# Timer_Register.net
KiCad netlist of a schematic drawn in Altium Designer
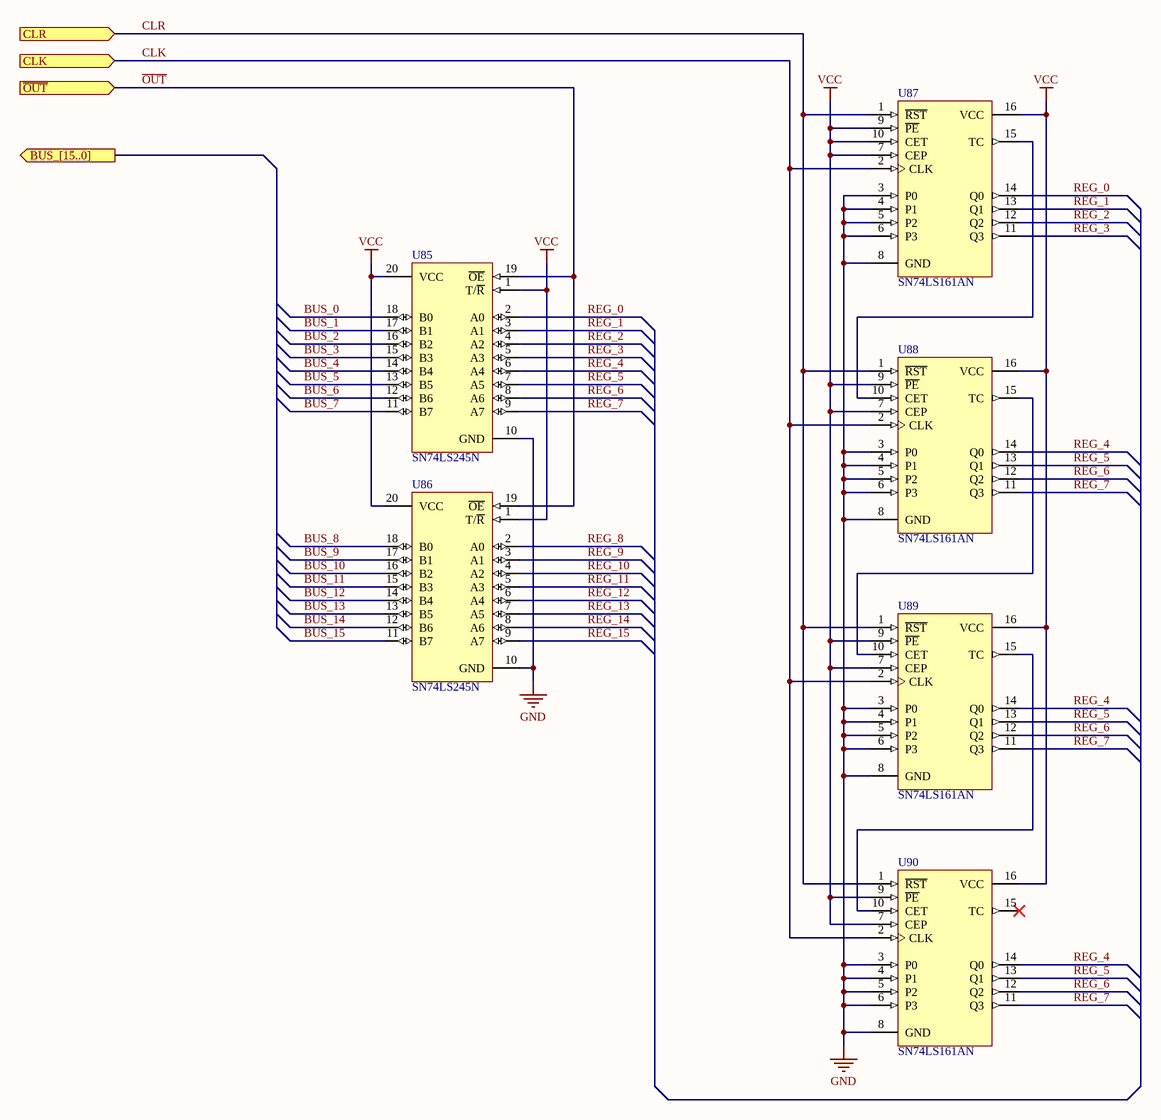
[diagram p0: Timer_Register.SchDoc]

(export (version "E")
  (design (tool "Eeschema 10.0.6"))
  (components
    (comp (ref "U85")
      (value "SN74LS245N")
      (footprint "N020")
      (description "Octal Bus Transceiver with 3-State Outputs")
      (fields (field (name "PUBLISHER") "Altium Limited"))
      (libsource (lib "TI Interface 8-Bit Line Transceiver") (part "SN74LS245N"))
    )
    (comp (ref "U86")
      (value "SN74LS245N")
      (footprint "N020")
      (description "Octal Bus Transceiver with 3-State Outputs")
      (fields (field (name "PUBLISHER") "Altium Limited"))
      (libsource (lib "TI Interface 8-Bit Line Transceiver") (part "SN74LS245N"))
    )
    (comp (ref "U87")
      (value "SN74LS161AN")
      (footprint "N016")
      (description "Synchronous 4-Bit Counter")
      (fields (field (name "PUBLISHER") "Altium Limited"))
      (libsource (lib "TI Logic Counter") (part "SN74LS161AN"))
    )
    (comp (ref "U88")
      (value "SN74LS161AN")
      (footprint "N016")
      (description "Synchronous 4-Bit Counter")
      (fields (field (name "PUBLISHER") "Altium Limited"))
      (libsource (lib "TI Logic Counter") (part "SN74LS161AN"))
    )
    (comp (ref "U89")
      (value "SN74LS161AN")
      (footprint "N016")
      (description "Synchronous 4-Bit Counter")
      (fields (field (name "PUBLISHER") "Altium Limited"))
      (libsource (lib "TI Logic Counter") (part "SN74LS161AN"))
    )
    (comp (ref "U90")
      (value "SN74LS161AN")
      (footprint "N016")
      (description "Synchronous 4-Bit Counter")
      (fields (field (name "PUBLISHER") "Altium Limited"))
      (libsource (lib "TI Logic Counter") (part "SN74LS161AN"))
    )
  )
  (nets
    (net (code "1") (name "/BUS_0") (class "Default")
      (node (ref "U85") (pin "18") (pinfunction "B0_18") (pintype "bidirectional"))
    )
    (net (code "2") (name "/BUS_1") (class "Default")
      (node (ref "U85") (pin "17") (pinfunction "B1_17") (pintype "bidirectional"))
    )
    (net (code "3") (name "/BUS_2") (class "Default")
      (node (ref "U85") (pin "16") (pinfunction "B2_16") (pintype "bidirectional"))
    )
    (net (code "4") (name "/BUS_3") (class "Default")
      (node (ref "U85") (pin "15") (pinfunction "B3_15") (pintype "bidirectional"))
    )
    (net (code "5") (name "/BUS_4") (class "Default")
      (node (ref "U85") (pin "14") (pinfunction "B4_14") (pintype "bidirectional"))
    )
    (net (code "6") (name "/BUS_5") (class "Default")
      (node (ref "U85") (pin "13") (pinfunction "B5_13") (pintype "bidirectional"))
    )
    (net (code "7") (name "/BUS_6") (class "Default")
      (node (ref "U85") (pin "12") (pinfunction "B6_12") (pintype "bidirectional"))
    )
    (net (code "8") (name "/BUS_7") (class "Default")
      (node (ref "U85") (pin "11") (pinfunction "B7_11") (pintype "bidirectional"))
    )
    (net (code "9") (name "/BUS_8") (class "Default")
      (node (ref "U86") (pin "18") (pinfunction "B0_18") (pintype "bidirectional"))
    )
    (net (code "10") (name "/BUS_9") (class "Default")
      (node (ref "U86") (pin "17") (pinfunction "B1_17") (pintype "bidirectional"))
    )
    (net (code "11") (name "/BUS_10") (class "Default")
      (node (ref "U86") (pin "16") (pinfunction "B2_16") (pintype "bidirectional"))
    )
    (net (code "12") (name "/BUS_11") (class "Default")
      (node (ref "U86") (pin "15") (pinfunction "B3_15") (pintype "bidirectional"))
    )
    (net (code "13") (name "/BUS_12") (class "Default")
      (node (ref "U86") (pin "14") (pinfunction "B4_14") (pintype "bidirectional"))
    )
    (net (code "14") (name "/BUS_13") (class "Default")
      (node (ref "U86") (pin "13") (pinfunction "B5_13") (pintype "bidirectional"))
    )
    (net (code "15") (name "/BUS_14") (class "Default")
      (node (ref "U86") (pin "12") (pinfunction "B6_12") (pintype "bidirectional"))
    )
    (net (code "16") (name "/BUS_15") (class "Default")
      (node (ref "U86") (pin "11") (pinfunction "B7_11") (pintype "bidirectional"))
    )
    (net (code "18") (name "/CLK") (class "Default")
      (node (ref "U87") (pin "2") (pinfunction "CLK_2") (pintype "input"))
      (node (ref "U88") (pin "2") (pinfunction "CLK_2") (pintype "input"))
      (node (ref "U89") (pin "2") (pinfunction "CLK_2") (pintype "input"))
      (node (ref "U90") (pin "2") (pinfunction "CLK_2") (pintype "input"))
    )
    (net (code "19") (name "/CLR") (class "Default")
      (node (ref "U87") (pin "1") (pinfunction "~{RST}_1") (pintype "input"))
      (node (ref "U88") (pin "1") (pinfunction "~{RST}_1") (pintype "input"))
      (node (ref "U89") (pin "1") (pinfunction "~{RST}_1") (pintype "input"))
      (node (ref "U90") (pin "1") (pinfunction "~{RST}_1") (pintype "input"))
    )
    (net (code "20") (name "/REG_0") (class "Default")
      (node (ref "U85") (pin "2") (pinfunction "A0_2") (pintype "bidirectional"))
      (node (ref "U87") (pin "14") (pinfunction "Q0_14") (pintype "output"))
    )
    (net (code "21") (name "/REG_1") (class "Default")
      (node (ref "U85") (pin "3") (pinfunction "A1_3") (pintype "bidirectional"))
      (node (ref "U87") (pin "13") (pinfunction "Q1_13") (pintype "output"))
    )
    (net (code "22") (name "/REG_2") (class "Default")
      (node (ref "U85") (pin "4") (pinfunction "A2_4") (pintype "bidirectional"))
      (node (ref "U87") (pin "12") (pinfunction "Q2_12") (pintype "output"))
    )
    (net (code "23") (name "/REG_3") (class "Default")
      (node (ref "U85") (pin "5") (pinfunction "A3_5") (pintype "bidirectional"))
      (node (ref "U87") (pin "11") (pinfunction "Q3_11") (pintype "output"))
    )
    (net (code "24") (name "/REG_4") (class "Default")
      (node (ref "U85") (pin "6") (pinfunction "A4_6") (pintype "bidirectional"))
      (node (ref "U88") (pin "14") (pinfunction "Q0_14") (pintype "output"))
      (node (ref "U89") (pin "14") (pinfunction "Q0_14") (pintype "output"))
      (node (ref "U90") (pin "14") (pinfunction "Q0_14") (pintype "output"))
    )
    (net (code "25") (name "/REG_5") (class "Default")
      (node (ref "U85") (pin "7") (pinfunction "A5_7") (pintype "bidirectional"))
      (node (ref "U88") (pin "13") (pinfunction "Q1_13") (pintype "output"))
      (node (ref "U89") (pin "13") (pinfunction "Q1_13") (pintype "output"))
      (node (ref "U90") (pin "13") (pinfunction "Q1_13") (pintype "output"))
    )
    (net (code "26") (name "/REG_6") (class "Default")
      (node (ref "U85") (pin "8") (pinfunction "A6_8") (pintype "bidirectional"))
      (node (ref "U88") (pin "12") (pinfunction "Q2_12") (pintype "output"))
      (node (ref "U89") (pin "12") (pinfunction "Q2_12") (pintype "output"))
      (node (ref "U90") (pin "12") (pinfunction "Q2_12") (pintype "output"))
    )
    (net (code "27") (name "/REG_7") (class "Default")
      (node (ref "U85") (pin "9") (pinfunction "A7_9") (pintype "bidirectional"))
      (node (ref "U88") (pin "11") (pinfunction "Q3_11") (pintype "output"))
      (node (ref "U89") (pin "11") (pinfunction "Q3_11") (pintype "output"))
      (node (ref "U90") (pin "11") (pinfunction "Q3_11") (pintype "output"))
    )
    (net (code "28") (name "/REG_8") (class "Default")
      (node (ref "U86") (pin "2") (pinfunction "A0_2") (pintype "bidirectional"))
    )
    (net (code "29") (name "/REG_9") (class "Default")
      (node (ref "U86") (pin "3") (pinfunction "A1_3") (pintype "bidirectional"))
    )
    (net (code "30") (name "/REG_10") (class "Default")
      (node (ref "U86") (pin "4") (pinfunction "A2_4") (pintype "bidirectional"))
    )
    (net (code "31") (name "/REG_11") (class "Default")
      (node (ref "U86") (pin "5") (pinfunction "A3_5") (pintype "bidirectional"))
    )
    (net (code "32") (name "/REG_12") (class "Default")
      (node (ref "U86") (pin "6") (pinfunction "A4_6") (pintype "bidirectional"))
    )
    (net (code "33") (name "/REG_13") (class "Default")
      (node (ref "U86") (pin "7") (pinfunction "A5_7") (pintype "bidirectional"))
    )
    (net (code "34") (name "/REG_14") (class "Default")
      (node (ref "U86") (pin "8") (pinfunction "A6_8") (pintype "bidirectional"))
    )
    (net (code "35") (name "/REG_15") (class "Default")
      (node (ref "U86") (pin "9") (pinfunction "A7_9") (pintype "bidirectional"))
    )
    (net (code "36") (name "/~{OUT}") (class "Default")
      (node (ref "U85") (pin "19") (pinfunction "~{OE}_19") (pintype "input"))
      (node (ref "U86") (pin "19") (pinfunction "~{OE}_19") (pintype "input"))
    )
    (net (code "37") (name "GND") (class "Default")
      (node (ref "U85") (pin "10") (pinfunction "GND_10") (pintype "power_in"))
      (node (ref "U86") (pin "10") (pinfunction "GND_10") (pintype "power_in"))
      (node (ref "U87") (pin "3") (pinfunction "P0_3") (pintype "input"))
      (node (ref "U87") (pin "4") (pinfunction "P1_4") (pintype "input"))
      (node (ref "U87") (pin "5") (pinfunction "P2_5") (pintype "input"))
      (node (ref "U87") (pin "6") (pinfunction "P3_6") (pintype "input"))
      (node (ref "U87") (pin "8") (pinfunction "GND_8") (pintype "power_in"))
      (node (ref "U88") (pin "3") (pinfunction "P0_3") (pintype "input"))
      (node (ref "U88") (pin "4") (pinfunction "P1_4") (pintype "input"))
      (node (ref "U88") (pin "5") (pinfunction "P2_5") (pintype "input"))
      (node (ref "U88") (pin "6") (pinfunction "P3_6") (pintype "input"))
      (node (ref "U88") (pin "8") (pinfunction "GND_8") (pintype "power_in"))
      (node (ref "U89") (pin "3") (pinfunction "P0_3") (pintype "input"))
      (node (ref "U89") (pin "4") (pinfunction "P1_4") (pintype "input"))
      (node (ref "U89") (pin "5") (pinfunction "P2_5") (pintype "input"))
      (node (ref "U89") (pin "6") (pinfunction "P3_6") (pintype "input"))
      (node (ref "U89") (pin "8") (pinfunction "GND_8") (pintype "power_in"))
      (node (ref "U90") (pin "3") (pinfunction "P0_3") (pintype "input"))
      (node (ref "U90") (pin "4") (pinfunction "P1_4") (pintype "input"))
      (node (ref "U90") (pin "5") (pinfunction "P2_5") (pintype "input"))
      (node (ref "U90") (pin "6") (pinfunction "P3_6") (pintype "input"))
      (node (ref "U90") (pin "8") (pinfunction "GND_8") (pintype "power_in"))
    )
    (net (code "38") (name "Net-(U87-TC)") (class "Default")
      (node (ref "U87") (pin "15") (pinfunction "TC_15") (pintype "output"))
      (node (ref "U88") (pin "10") (pinfunction "CET_10") (pintype "input"))
    )
    (net (code "39") (name "Net-(U88-TC)") (class "Default")
      (node (ref "U88") (pin "15") (pinfunction "TC_15") (pintype "output"))
      (node (ref "U89") (pin "10") (pinfunction "CET_10") (pintype "input"))
    )
    (net (code "40") (name "Net-(U89-TC)") (class "Default")
      (node (ref "U89") (pin "15") (pinfunction "TC_15") (pintype "output"))
      (node (ref "U90") (pin "10") (pinfunction "CET_10") (pintype "input"))
    )
    (net (code "41") (name "VCC") (class "Default")
      (node (ref "U85") (pin "1") (pinfunction "T/~{R}_1") (pintype "input"))
      (node (ref "U85") (pin "20") (pinfunction "VCC_20") (pintype "power_in"))
      (node (ref "U86") (pin "1") (pinfunction "T/~{R}_1") (pintype "input"))
      (node (ref "U86") (pin "20") (pinfunction "VCC_20") (pintype "power_in"))
      (node (ref "U87") (pin "10") (pinfunction "CET_10") (pintype "input"))
      (node (ref "U87") (pin "16") (pinfunction "VCC_16") (pintype "power_in"))
      (node (ref "U87") (pin "7") (pinfunction "CEP_7") (pintype "input"))
      (node (ref "U87") (pin "9") (pinfunction "~{PE}_9") (pintype "input"))
      (node (ref "U88") (pin "16") (pinfunction "VCC_16") (pintype "power_in"))
      (node (ref "U88") (pin "7") (pinfunction "CEP_7") (pintype "input"))
      (node (ref "U88") (pin "9") (pinfunction "~{PE}_9") (pintype "input"))
      (node (ref "U89") (pin "16") (pinfunction "VCC_16") (pintype "power_in"))
      (node (ref "U89") (pin "7") (pinfunction "CEP_7") (pintype "input"))
      (node (ref "U89") (pin "9") (pinfunction "~{PE}_9") (pintype "input"))
      (node (ref "U90") (pin "16") (pinfunction "VCC_16") (pintype "power_in"))
      (node (ref "U90") (pin "7") (pinfunction "CEP_7") (pintype "input"))
      (node (ref "U90") (pin "9") (pinfunction "~{PE}_9") (pintype "input"))
    )
    (net (code "42") (name "unconnected-(U90-TC-Pad15)") (class "Default")
      (node (ref "U90") (pin "15") (pinfunction "TC_15") (pintype "output+no_connect"))
    )
  )
)
